# LM2596.net
KiCad netlist of a schematic drawn in Altium Designer
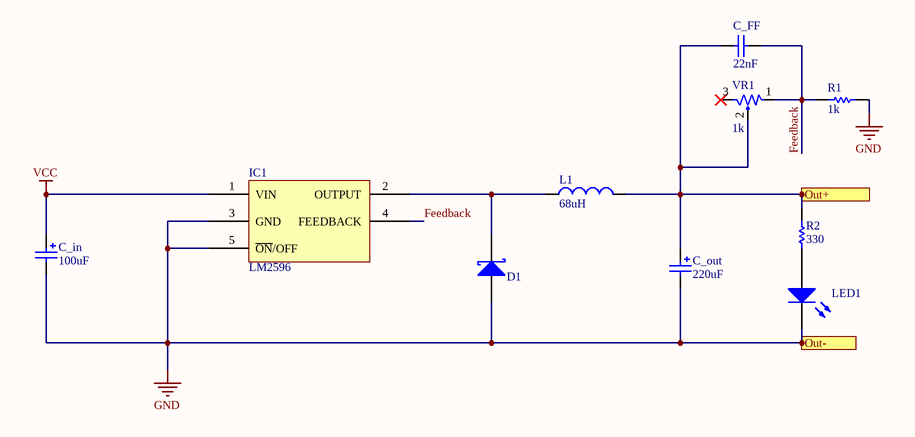
[diagram p0: LM2596.SchDoc]

(export (version "E")
  (design (tool "Eeschema 10.0.6"))
  (components
    (comp (ref "C_FF")
      (value "22nF")
      (footprint "CAP-0805")
      (libsource (lib "Altium_library_module_kit") (part "CAP-SMD-0805"))
    )
    (comp (ref "C_in")
      (value "100uF")
      (footprint "CAP-ALU")
      (libsource (lib "Altium_library_module_kit") (part "CAP-ALUM"))
    )
    (comp (ref "C_out")
      (value "220uF")
      (footprint "CAP-ALU")
      (libsource (lib "Altium_library_module_kit") (part "CAP-ALUM"))
    )
    (comp (ref "D1")
      (value "D Schottky")
      (footprint "SS34")
      (description "Schottky Diode")
      (fields (field (name "PUBLISHER") "Altium Limited"))
      (libsource (lib "PIF_Library") (part "D Schottky"))
    )
    (comp (ref "IC1")
      (value "LM2596")
      (footprint "LM2596")
      (libsource (lib "Altium_library_module_kit") (part "LM2596"))
    )
    (comp (ref "L1")
      (value "68uH")
      (footprint "INDUCTOR")
      (libsource (lib "Altium_library_module_kit") (part "INDUCTOR"))
    )
    (comp (ref "LED1")
      (value "~")
      (footprint "LED-0805")
      (libsource (lib "Altium_library_module_kit") (part "LED-0805"))
    )
    (comp (ref "R1")
      (value "1k")
      (footprint "RES-SMD-0805")
      (libsource (lib "Altium_library_module_kit") (part "RES-SMD-0805"))
    )
    (comp (ref "R2")
      (value "330")
      (footprint "RES-SMD-0805")
      (libsource (lib "Altium_library_module_kit") (part "RES-SMD-0805"))
    )
    (comp (ref "VR1")
      (value "1k")
      (footprint "Varistor")
      (libsource (lib "Altium_library_module_kit") (part "Varistor"))
    )
  )
  (nets
    (net (code "1") (name "/Feedback") (class "Default")
      (node (ref "C_FF") (pin "1") (pinfunction "1_1") (pintype "passive"))
      (node (ref "IC1") (pin "4") (pinfunction "FEEDBACK_4") (pintype "passive"))
      (node (ref "R1") (pin "2") (pinfunction "2_2") (pintype "passive"))
      (node (ref "VR1") (pin "1") (pinfunction "1_1") (pintype "passive"))
    )
    (net (code "2") (name "/Out+") (class "Default")
      (node (ref "C_FF") (pin "2") (pinfunction "2_2") (pintype "passive"))
      (node (ref "C_out") (pin "1") (pinfunction "1_1") (pintype "passive"))
      (node (ref "L1") (pin "2") (pinfunction "2_2") (pintype "passive"))
      (node (ref "R2") (pin "1") (pinfunction "1_1") (pintype "passive"))
      (node (ref "VR1") (pin "2") (pinfunction "2_2") (pintype "passive"))
    )
    (net (code "3") (name "GND") (class "Default")
      (node (ref "C_in") (pin "2") (pinfunction "2_2") (pintype "passive"))
      (node (ref "C_out") (pin "2") (pinfunction "2_2") (pintype "passive"))
      (node (ref "D1") (pin "1") (pinfunction "A_1") (pintype "passive"))
      (node (ref "IC1") (pin "3") (pinfunction "GND_3") (pintype "passive"))
      (node (ref "IC1") (pin "5") (pinfunction "~{ON}/OFF_5") (pintype "passive"))
      (node (ref "LED1") (pin "2") (pinfunction "K_2") (pintype "passive"))
      (node (ref "R1") (pin "1") (pinfunction "1_1") (pintype "passive"))
    )
    (net (code "4") (name "Net-(D1-K)") (class "Default")
      (node (ref "D1") (pin "2") (pinfunction "K_2") (pintype "passive"))
      (node (ref "IC1") (pin "2") (pinfunction "OUTPUT_2") (pintype "passive"))
      (node (ref "L1") (pin "1") (pinfunction "1_1") (pintype "passive"))
    )
    (net (code "5") (name "Net-(LED1-A)") (class "Default")
      (node (ref "LED1") (pin "1") (pinfunction "A_1") (pintype "passive"))
      (node (ref "R2") (pin "2") (pinfunction "2_2") (pintype "passive"))
    )
    (net (code "6") (name "VCC") (class "Default")
      (node (ref "C_in") (pin "1") (pinfunction "1_1") (pintype "passive"))
      (node (ref "IC1") (pin "1") (pinfunction "VIN_1") (pintype "passive"))
    )
    (net (code "7") (name "unconnected-(VR1-Pad3)") (class "Default")
      (node (ref "VR1") (pin "3") (pinfunction "3_3") (pintype "passive+no_connect"))
    )
  )
)
